# Sheet_1.net
KiCad netlist of a schematic drawn in Altium Designer
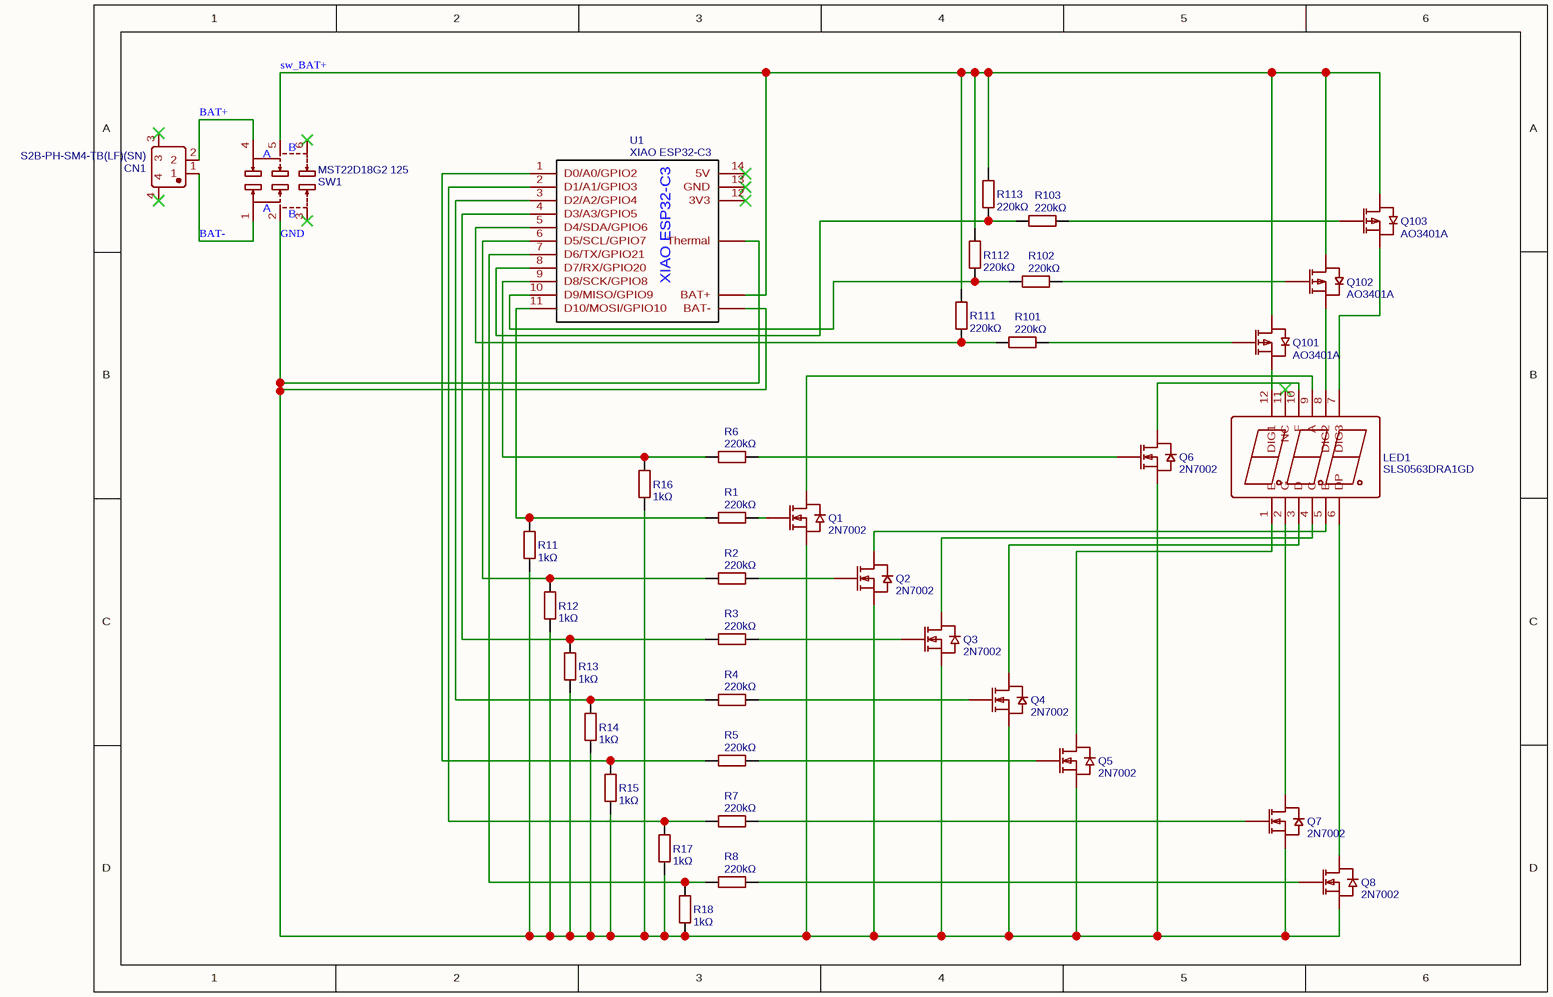
[diagram p0: Sheet_1.schdoc]

(export (version "E")
  (design (tool "Eeschema 10.0.6"))
  (components
    (comp (ref "CN1")
      (value "S2B-PH-SM4-TB(LF)(SN)")
      (fields (field (name "BOM_SUPPLIER PART") "C295747") (field (name "CONTRIBUTOR") "LCSC"))
      (libsource (lib "altium-import") (part "root_0_S2B-PH-SM4-TB(LF)(SN)_"))
    )
    (comp (ref "LED1")
      (value "SLS0563DRA1GD")
      (fields (field (name "BOM_SUPPLIER PART") "C226009") (field (name "CONTRIBUTOR") "LCSC"))
      (libsource (lib "altium-import") (part "root_0_SLS0563DRA1GD_"))
    )
    (comp (ref "Q1")
      (value "2N7002")
      (fields (field (name "BOM_SUPPLIER PART") "C8545"))
      (libsource (lib "altium-import") (part "root_0_2N7002_"))
    )
    (comp (ref "Q2")
      (value "2N7002")
      (fields (field (name "BOM_SUPPLIER PART") "C8545"))
      (libsource (lib "altium-import") (part "root_0_2N7002_"))
    )
    (comp (ref "Q3")
      (value "2N7002")
      (fields (field (name "BOM_SUPPLIER PART") "C8545"))
      (libsource (lib "altium-import") (part "root_0_2N7002_"))
    )
    (comp (ref "Q4")
      (value "2N7002")
      (fields (field (name "BOM_SUPPLIER PART") "C8545"))
      (libsource (lib "altium-import") (part "root_0_2N7002_"))
    )
    (comp (ref "Q5")
      (value "2N7002")
      (fields (field (name "BOM_SUPPLIER PART") "C8545"))
      (libsource (lib "altium-import") (part "root_0_2N7002_"))
    )
    (comp (ref "Q6")
      (value "2N7002")
      (fields (field (name "BOM_SUPPLIER PART") "C8545"))
      (libsource (lib "altium-import") (part "root_0_2N7002_"))
    )
    (comp (ref "Q7")
      (value "2N7002")
      (fields (field (name "BOM_SUPPLIER PART") "C8545"))
      (libsource (lib "altium-import") (part "root_0_2N7002_"))
    )
    (comp (ref "Q8")
      (value "2N7002")
      (fields (field (name "BOM_SUPPLIER PART") "C8545"))
      (libsource (lib "altium-import") (part "root_0_2N7002_"))
    )
    (comp (ref "Q101")
      (value "AO3401A")
      (fields (field (name "BOM_SUPPLIER PART") "C15127"))
      (libsource (lib "altium-import") (part "root_0_AO3401A_"))
    )
    (comp (ref "Q102")
      (value "AO3401A")
      (fields (field (name "BOM_SUPPLIER PART") "C15127"))
      (libsource (lib "altium-import") (part "root_0_AO3401A_"))
    )
    (comp (ref "Q103")
      (value "AO3401A")
      (fields (field (name "BOM_SUPPLIER PART") "C15127"))
      (libsource (lib "altium-import") (part "root_0_AO3401A_"))
    )
    (comp (ref "R1")
      (value "220kΩ")
      (fields
        (field (name "BOM_MANUFACTURER PART") "0603WAF2203T5E")
        (field (name "BOM_SUPPLIER PART") "C22961")
      )
      (libsource (lib "altium-import") (part "root_0_220kΩ_"))
    )
    (comp (ref "R2")
      (value "220kΩ")
      (fields
        (field (name "BOM_MANUFACTURER PART") "0603WAF2203T5E")
        (field (name "BOM_SUPPLIER PART") "C22961")
      )
      (libsource (lib "altium-import") (part "root_0_220kΩ_"))
    )
    (comp (ref "R3")
      (value "220kΩ")
      (fields
        (field (name "BOM_MANUFACTURER PART") "0603WAF2203T5E")
        (field (name "BOM_SUPPLIER PART") "C22961")
      )
      (libsource (lib "altium-import") (part "root_0_220kΩ_"))
    )
    (comp (ref "R4")
      (value "220kΩ")
      (fields
        (field (name "BOM_MANUFACTURER PART") "0603WAF2203T5E")
        (field (name "BOM_SUPPLIER PART") "C22961")
      )
      (libsource (lib "altium-import") (part "root_0_220kΩ_"))
    )
    (comp (ref "R5")
      (value "220kΩ")
      (fields
        (field (name "BOM_MANUFACTURER PART") "0603WAF2203T5E")
        (field (name "BOM_SUPPLIER PART") "C22961")
      )
      (libsource (lib "altium-import") (part "root_0_220kΩ_"))
    )
    (comp (ref "R6")
      (value "220kΩ")
      (fields
        (field (name "BOM_MANUFACTURER PART") "0603WAF2203T5E")
        (field (name "BOM_SUPPLIER PART") "C22961")
      )
      (libsource (lib "altium-import") (part "root_0_220kΩ_"))
    )
    (comp (ref "R7")
      (value "220kΩ")
      (fields
        (field (name "BOM_MANUFACTURER PART") "0603WAF2203T5E")
        (field (name "BOM_SUPPLIER PART") "C22961")
      )
      (libsource (lib "altium-import") (part "root_0_220kΩ_"))
    )
    (comp (ref "R8")
      (value "220kΩ")
      (fields
        (field (name "BOM_MANUFACTURER PART") "0603WAF2203T5E")
        (field (name "BOM_SUPPLIER PART") "C22961")
      )
      (libsource (lib "altium-import") (part "root_0_220kΩ_"))
    )
    (comp (ref "R11")
      (value "1kΩ")
      (fields
        (field (name "BOM_MANUFACTURER PART") "0603WAF1001T5E")
        (field (name "BOM_SUPPLIER PART") "C21190")
      )
      (libsource (lib "altium-import") (part "root_1_1kΩ_"))
    )
    (comp (ref "R12")
      (value "1kΩ")
      (fields
        (field (name "BOM_MANUFACTURER PART") "0603WAF1001T5E")
        (field (name "BOM_SUPPLIER PART") "C21190")
      )
      (libsource (lib "altium-import") (part "root_1_1kΩ_"))
    )
    (comp (ref "R13")
      (value "1kΩ")
      (fields
        (field (name "BOM_MANUFACTURER PART") "0603WAF1001T5E")
        (field (name "BOM_SUPPLIER PART") "C21190")
      )
      (libsource (lib "altium-import") (part "root_1_1kΩ_"))
    )
    (comp (ref "R14")
      (value "1kΩ")
      (fields
        (field (name "BOM_MANUFACTURER PART") "0603WAF1001T5E")
        (field (name "BOM_SUPPLIER PART") "C21190")
      )
      (libsource (lib "altium-import") (part "root_1_1kΩ_"))
    )
    (comp (ref "R15")
      (value "1kΩ")
      (fields
        (field (name "BOM_MANUFACTURER PART") "0603WAF1001T5E")
        (field (name "BOM_SUPPLIER PART") "C21190")
      )
      (libsource (lib "altium-import") (part "root_1_1kΩ_"))
    )
    (comp (ref "R16")
      (value "1kΩ")
      (fields
        (field (name "BOM_MANUFACTURER PART") "0603WAF1001T5E")
        (field (name "BOM_SUPPLIER PART") "C21190")
      )
      (libsource (lib "altium-import") (part "root_1_1kΩ_"))
    )
    (comp (ref "R17")
      (value "1kΩ")
      (fields
        (field (name "BOM_MANUFACTURER PART") "0603WAF1001T5E")
        (field (name "BOM_SUPPLIER PART") "C21190")
      )
      (libsource (lib "altium-import") (part "root_1_1kΩ_"))
    )
    (comp (ref "R18")
      (value "1kΩ")
      (fields
        (field (name "BOM_MANUFACTURER PART") "0603WAF1001T5E")
        (field (name "BOM_SUPPLIER PART") "C21190")
      )
      (libsource (lib "altium-import") (part "root_1_1kΩ_"))
    )
    (comp (ref "R101")
      (value "220kΩ")
      (fields
        (field (name "BOM_MANUFACTURER PART") "0603WAF2203T5E")
        (field (name "BOM_SUPPLIER PART") "C22961")
      )
      (libsource (lib "altium-import") (part "root_2_220kΩ_"))
    )
    (comp (ref "R102")
      (value "220kΩ")
      (fields
        (field (name "BOM_MANUFACTURER PART") "0603WAF2203T5E")
        (field (name "BOM_SUPPLIER PART") "C22961")
      )
      (libsource (lib "altium-import") (part "root_2_220kΩ_"))
    )
    (comp (ref "R103")
      (value "220kΩ")
      (fields
        (field (name "BOM_MANUFACTURER PART") "0603WAF2203T5E")
        (field (name "BOM_SUPPLIER PART") "C22961")
      )
      (libsource (lib "altium-import") (part "root_2_220kΩ_"))
    )
    (comp (ref "R111")
      (value "220kΩ")
      (fields
        (field (name "BOM_MANUFACTURER PART") "0603WAF2203T5E")
        (field (name "BOM_SUPPLIER PART") "C22961")
      )
      (libsource (lib "altium-import") (part "root_1_220kΩ_"))
    )
    (comp (ref "R112")
      (value "220kΩ")
      (fields
        (field (name "BOM_MANUFACTURER PART") "0603WAF2203T5E")
        (field (name "BOM_SUPPLIER PART") "C22961")
      )
      (libsource (lib "altium-import") (part "root_1_220kΩ_"))
    )
    (comp (ref "R113")
      (value "220kΩ")
      (fields
        (field (name "BOM_MANUFACTURER PART") "0603WAF2203T5E")
        (field (name "BOM_SUPPLIER PART") "C22961")
      )
      (libsource (lib "altium-import") (part "root_1_220kΩ_"))
    )
    (comp (ref "SW1")
      (value "MST22D18G2 125")
      (fields (field (name "BOM_SUPPLIER PART") "C2906280") (field (name "CONTRIBUTOR") "LCSC"))
      (libsource (lib "altium-import") (part "root_0_MST22D18G2 125_"))
    )
    (comp (ref "U1")
      (value "XIAO ESP32-C3")
      (fields
        (field (name "BOM_MANUFACTURER PART") "XIAO-ESP32C3")
        (field (name "CONTRIBUTOR") "mlp-easyeda")
      )
      (libsource (lib "altium-import") (part "root_0_XIAO ESP32-C3_"))
    )
  )
  (nets
    (net (code "1") (name "/BAT+") (class "Default")
      (node (ref "CN1") (pin "2") (pinfunction "2_2") (pintype "passive"))
      (node (ref "SW1") (pin "4") (pinfunction "4_4") (pintype "passive"))
    )
    (net (code "2") (name "/BAT-") (class "Default")
      (node (ref "CN1") (pin "1") (pinfunction "1_1") (pintype "passive"))
      (node (ref "SW1") (pin "1") (pinfunction "1_1") (pintype "passive"))
    )
    (net (code "3") (name "/GND") (class "Default")
      (node (ref "Q1") (pin "2") (pinfunction "S_2") (pintype "passive"))
      (node (ref "Q2") (pin "2") (pinfunction "S_2") (pintype "passive"))
      (node (ref "Q3") (pin "2") (pinfunction "S_2") (pintype "passive"))
      (node (ref "Q4") (pin "2") (pinfunction "S_2") (pintype "passive"))
      (node (ref "Q5") (pin "2") (pinfunction "S_2") (pintype "passive"))
      (node (ref "Q6") (pin "2") (pinfunction "S_2") (pintype "passive"))
      (node (ref "Q7") (pin "2") (pinfunction "S_2") (pintype "passive"))
      (node (ref "Q8") (pin "2") (pinfunction "S_2") (pintype "passive"))
      (node (ref "R11") (pin "1") (pinfunction "1_1") (pintype "passive"))
      (node (ref "R12") (pin "1") (pinfunction "1_1") (pintype "passive"))
      (node (ref "R13") (pin "1") (pinfunction "1_1") (pintype "passive"))
      (node (ref "R14") (pin "1") (pinfunction "1_1") (pintype "passive"))
      (node (ref "R15") (pin "1") (pinfunction "1_1") (pintype "passive"))
      (node (ref "R16") (pin "1") (pinfunction "1_1") (pintype "passive"))
      (node (ref "R17") (pin "1") (pinfunction "1_1") (pintype "passive"))
      (node (ref "R18") (pin "1") (pinfunction "1_1") (pintype "passive"))
      (node (ref "SW1") (pin "2") (pinfunction "2_2") (pintype "passive"))
      (node (ref "U1") (pin "BAT-") (pinfunction "BAT-_BAT-") (pintype "passive"))
      (node (ref "U1") (pin "Thermal") (pinfunction "Thermal_Thermal") (pintype "passive"))
    )
    (net (code "4") (name "/sw_BAT+") (class "Default")
      (node (ref "Q101") (pin "3") (pinfunction "D_3") (pintype "passive"))
      (node (ref "Q102") (pin "3") (pinfunction "D_3") (pintype "passive"))
      (node (ref "Q103") (pin "3") (pinfunction "D_3") (pintype "passive"))
      (node (ref "R111") (pin "2") (pinfunction "2_2") (pintype "passive"))
      (node (ref "R112") (pin "2") (pinfunction "2_2") (pintype "passive"))
      (node (ref "R113") (pin "2") (pinfunction "2_2") (pintype "passive"))
      (node (ref "SW1") (pin "5") (pinfunction "5_5") (pintype "passive"))
      (node (ref "U1") (pin "BAT+") (pinfunction "BAT+_BAT+") (pintype "passive"))
    )
    (net (code "5") (name "Net-(LED1-A)") (class "Default")
      (node (ref "LED1") (pin "9") (pinfunction "A_9") (pintype "passive"))
      (node (ref "Q1") (pin "3") (pinfunction "D_3") (pintype "passive"))
    )
    (net (code "6") (name "Net-(LED1-B)") (class "Default")
      (node (ref "LED1") (pin "5") (pinfunction "B_5") (pintype "passive"))
      (node (ref "Q2") (pin "3") (pinfunction "D_3") (pintype "passive"))
    )
    (net (code "7") (name "Net-(LED1-C)") (class "Default")
      (node (ref "LED1") (pin "4") (pinfunction "C_4") (pintype "passive"))
      (node (ref "Q3") (pin "3") (pinfunction "D_3") (pintype "passive"))
    )
    (net (code "8") (name "Net-(LED1-D)") (class "Default")
      (node (ref "LED1") (pin "3") (pinfunction "D_3") (pintype "passive"))
      (node (ref "Q4") (pin "3") (pinfunction "D_3") (pintype "passive"))
    )
    (net (code "9") (name "Net-(LED1-DIG1)") (class "Default")
      (node (ref "LED1") (pin "12") (pinfunction "DIG1_12") (pintype "passive"))
      (node (ref "Q101") (pin "2") (pinfunction "S_2") (pintype "passive"))
    )
    (net (code "10") (name "Net-(LED1-DIG2)") (class "Default")
      (node (ref "LED1") (pin "8") (pinfunction "DIG2_8") (pintype "passive"))
      (node (ref "Q102") (pin "2") (pinfunction "S_2") (pintype "passive"))
    )
    (net (code "11") (name "Net-(LED1-DIG3)") (class "Default")
      (node (ref "LED1") (pin "7") (pinfunction "DIG3_7") (pintype "passive"))
      (node (ref "Q103") (pin "2") (pinfunction "S_2") (pintype "passive"))
    )
    (net (code "12") (name "Net-(LED1-DP)") (class "Default")
      (node (ref "LED1") (pin "6") (pinfunction "DP_6") (pintype "passive"))
      (node (ref "Q8") (pin "3") (pinfunction "D_3") (pintype "passive"))
    )
    (net (code "13") (name "Net-(LED1-E)") (class "Default")
      (node (ref "LED1") (pin "1") (pinfunction "E_1") (pintype "passive"))
      (node (ref "Q5") (pin "3") (pinfunction "D_3") (pintype "passive"))
    )
    (net (code "14") (name "Net-(LED1-F)") (class "Default")
      (node (ref "LED1") (pin "10") (pinfunction "F_10") (pintype "passive"))
      (node (ref "Q6") (pin "3") (pinfunction "D_3") (pintype "passive"))
    )
    (net (code "15") (name "Net-(LED1-G)") (class "Default")
      (node (ref "LED1") (pin "2") (pinfunction "G_2") (pintype "passive"))
      (node (ref "Q7") (pin "3") (pinfunction "D_3") (pintype "passive"))
    )
    (net (code "16") (name "Net-(Q1-G)") (class "Default")
      (node (ref "Q1") (pin "1") (pinfunction "G_1") (pintype "passive"))
      (node (ref "R1") (pin "2") (pinfunction "2_2") (pintype "passive"))
    )
    (net (code "17") (name "Net-(Q2-G)") (class "Default")
      (node (ref "Q2") (pin "1") (pinfunction "G_1") (pintype "passive"))
      (node (ref "R2") (pin "2") (pinfunction "2_2") (pintype "passive"))
    )
    (net (code "18") (name "Net-(Q3-G)") (class "Default")
      (node (ref "Q3") (pin "1") (pinfunction "G_1") (pintype "passive"))
      (node (ref "R3") (pin "2") (pinfunction "2_2") (pintype "passive"))
    )
    (net (code "19") (name "Net-(Q4-G)") (class "Default")
      (node (ref "Q4") (pin "1") (pinfunction "G_1") (pintype "passive"))
      (node (ref "R4") (pin "2") (pinfunction "2_2") (pintype "passive"))
    )
    (net (code "20") (name "Net-(Q5-G)") (class "Default")
      (node (ref "Q5") (pin "1") (pinfunction "G_1") (pintype "passive"))
      (node (ref "R5") (pin "2") (pinfunction "2_2") (pintype "passive"))
    )
    (net (code "21") (name "Net-(Q6-G)") (class "Default")
      (node (ref "Q6") (pin "1") (pinfunction "G_1") (pintype "passive"))
      (node (ref "R6") (pin "2") (pinfunction "2_2") (pintype "passive"))
    )
    (net (code "22") (name "Net-(Q7-G)") (class "Default")
      (node (ref "Q7") (pin "1") (pinfunction "G_1") (pintype "passive"))
      (node (ref "R7") (pin "2") (pinfunction "2_2") (pintype "passive"))
    )
    (net (code "23") (name "Net-(Q8-G)") (class "Default")
      (node (ref "Q8") (pin "1") (pinfunction "G_1") (pintype "passive"))
      (node (ref "R8") (pin "2") (pinfunction "2_2") (pintype "passive"))
    )
    (net (code "24") (name "Net-(Q101-G)") (class "Default")
      (node (ref "Q101") (pin "1") (pinfunction "G_1") (pintype "passive"))
      (node (ref "R101") (pin "1") (pinfunction "1_1") (pintype "passive"))
    )
    (net (code "25") (name "Net-(Q102-G)") (class "Default")
      (node (ref "Q102") (pin "1") (pinfunction "G_1") (pintype "passive"))
      (node (ref "R102") (pin "1") (pinfunction "1_1") (pintype "passive"))
    )
    (net (code "26") (name "Net-(Q103-G)") (class "Default")
      (node (ref "Q103") (pin "1") (pinfunction "G_1") (pintype "passive"))
      (node (ref "R103") (pin "1") (pinfunction "1_1") (pintype "passive"))
    )
    (net (code "27") (name "Net-(U1-D0{slash}A0{slash}GPIO2)") (class "Default")
      (node (ref "R15") (pin "2") (pinfunction "2_2") (pintype "passive"))
      (node (ref "R5") (pin "1") (pinfunction "1_1") (pintype "passive"))
      (node (ref "U1") (pin "1") (pinfunction "D0/A0/GPIO2_1") (pintype "passive"))
    )
    (net (code "28") (name "Net-(U1-D1{slash}A1{slash}GPIO3)") (class "Default")
      (node (ref "R17") (pin "2") (pinfunction "2_2") (pintype "passive"))
      (node (ref "R7") (pin "1") (pinfunction "1_1") (pintype "passive"))
      (node (ref "U1") (pin "2") (pinfunction "D1/A1/GPIO3_2") (pintype "passive"))
    )
    (net (code "29") (name "Net-(U1-D2{slash}A2{slash}GPIO4)") (class "Default")
      (node (ref "R14") (pin "2") (pinfunction "2_2") (pintype "passive"))
      (node (ref "R4") (pin "1") (pinfunction "1_1") (pintype "passive"))
      (node (ref "U1") (pin "3") (pinfunction "D2/A2/GPIO4_3") (pintype "passive"))
    )
    (net (code "30") (name "Net-(U1-D3{slash}A3{slash}GPIO5)") (class "Default")
      (node (ref "R13") (pin "2") (pinfunction "2_2") (pintype "passive"))
      (node (ref "R3") (pin "1") (pinfunction "1_1") (pintype "passive"))
      (node (ref "U1") (pin "4") (pinfunction "D3/A3/GPIO5_4") (pintype "passive"))
    )
    (net (code "31") (name "Net-(U1-D4{slash}SDA{slash}GPIO6)") (class "Default")
      (node (ref "R101") (pin "2") (pinfunction "2_2") (pintype "passive"))
      (node (ref "R111") (pin "1") (pinfunction "1_1") (pintype "passive"))
      (node (ref "U1") (pin "5") (pinfunction "D4/SDA/GPIO6_5") (pintype "passive"))
    )
    (net (code "32") (name "Net-(U1-D5{slash}SCL{slash}GPIO7)") (class "Default")
      (node (ref "R12") (pin "2") (pinfunction "2_2") (pintype "passive"))
      (node (ref "R2") (pin "1") (pinfunction "1_1") (pintype "passive"))
      (node (ref "U1") (pin "6") (pinfunction "D5/SCL/GPIO7_6") (pintype "passive"))
    )
    (net (code "33") (name "Net-(U1-D6{slash}TX{slash}GPIO21)") (class "Default")
      (node (ref "R18") (pin "2") (pinfunction "2_2") (pintype "passive"))
      (node (ref "R8") (pin "1") (pinfunction "1_1") (pintype "passive"))
      (node (ref "U1") (pin "7") (pinfunction "D6/TX/GPIO21_7") (pintype "passive"))
    )
    (net (code "34") (name "Net-(U1-D7{slash}RX{slash}GPIO20)") (class "Default")
      (node (ref "R103") (pin "2") (pinfunction "2_2") (pintype "passive"))
      (node (ref "R113") (pin "1") (pinfunction "1_1") (pintype "passive"))
      (node (ref "U1") (pin "8") (pinfunction "D7/RX/GPIO20_8") (pintype "passive"))
    )
    (net (code "35") (name "Net-(U1-D8{slash}SCK{slash}GPIO8)") (class "Default")
      (node (ref "R16") (pin "2") (pinfunction "2_2") (pintype "passive"))
      (node (ref "R6") (pin "1") (pinfunction "1_1") (pintype "passive"))
      (node (ref "U1") (pin "9") (pinfunction "D8/SCK/GPIO8_9") (pintype "passive"))
    )
    (net (code "36") (name "Net-(U1-D9{slash}MISO{slash}GPIO9)") (class "Default")
      (node (ref "R102") (pin "2") (pinfunction "2_2") (pintype "passive"))
      (node (ref "R112") (pin "1") (pinfunction "1_1") (pintype "passive"))
      (node (ref "U1") (pin "10") (pinfunction "D9/MISO/GPIO9_10") (pintype "passive"))
    )
    (net (code "37") (name "Net-(U1-D10{slash}MOSI{slash}GPIO10)") (class "Default")
      (node (ref "R1") (pin "1") (pinfunction "1_1") (pintype "passive"))
      (node (ref "R11") (pin "2") (pinfunction "2_2") (pintype "passive"))
      (node (ref "U1") (pin "11") (pinfunction "D10/MOSI/GPIO10_11") (pintype "passive"))
    )
    (net (code "38") (name "unconnected-(CN1-Pad3)") (class "Default")
      (node (ref "CN1") (pin "3") (pinfunction "3_3") (pintype "passive+no_connect"))
    )
    (net (code "39") (name "unconnected-(CN1-Pad4)") (class "Default")
      (node (ref "CN1") (pin "4") (pinfunction "4_4") (pintype "passive+no_connect"))
    )
    (net (code "40") (name "unconnected-(LED1-NC-Pad11)") (class "Default")
      (node (ref "LED1") (pin "11") (pinfunction "NC_11") (pintype "passive+no_connect"))
    )
    (net (code "41") (name "unconnected-(SW1-Pad3)") (class "Default")
      (node (ref "SW1") (pin "3") (pinfunction "3_3") (pintype "passive+no_connect"))
    )
    (net (code "42") (name "unconnected-(SW1-Pad6)") (class "Default")
      (node (ref "SW1") (pin "6") (pinfunction "6_6") (pintype "passive+no_connect"))
    )
    (net (code "43") (name "unconnected-(U1-3V3-Pad12)") (class "Default")
      (node (ref "U1") (pin "12") (pinfunction "3V3_12") (pintype "passive+no_connect"))
    )
    (net (code "44") (name "unconnected-(U1-5V-Pad14)") (class "Default")
      (node (ref "U1") (pin "14") (pinfunction "5V_14") (pintype "passive+no_connect"))
    )
    (net (code "45") (name "unconnected-(U1-GND-Pad13)") (class "Default")
      (node (ref "U1") (pin "13") (pinfunction "GND_13") (pintype "passive+no_connect"))
    )
  )
)
